# polarization_switch_mid.net
KiCad netlist of a schematic drawn in EAGLE
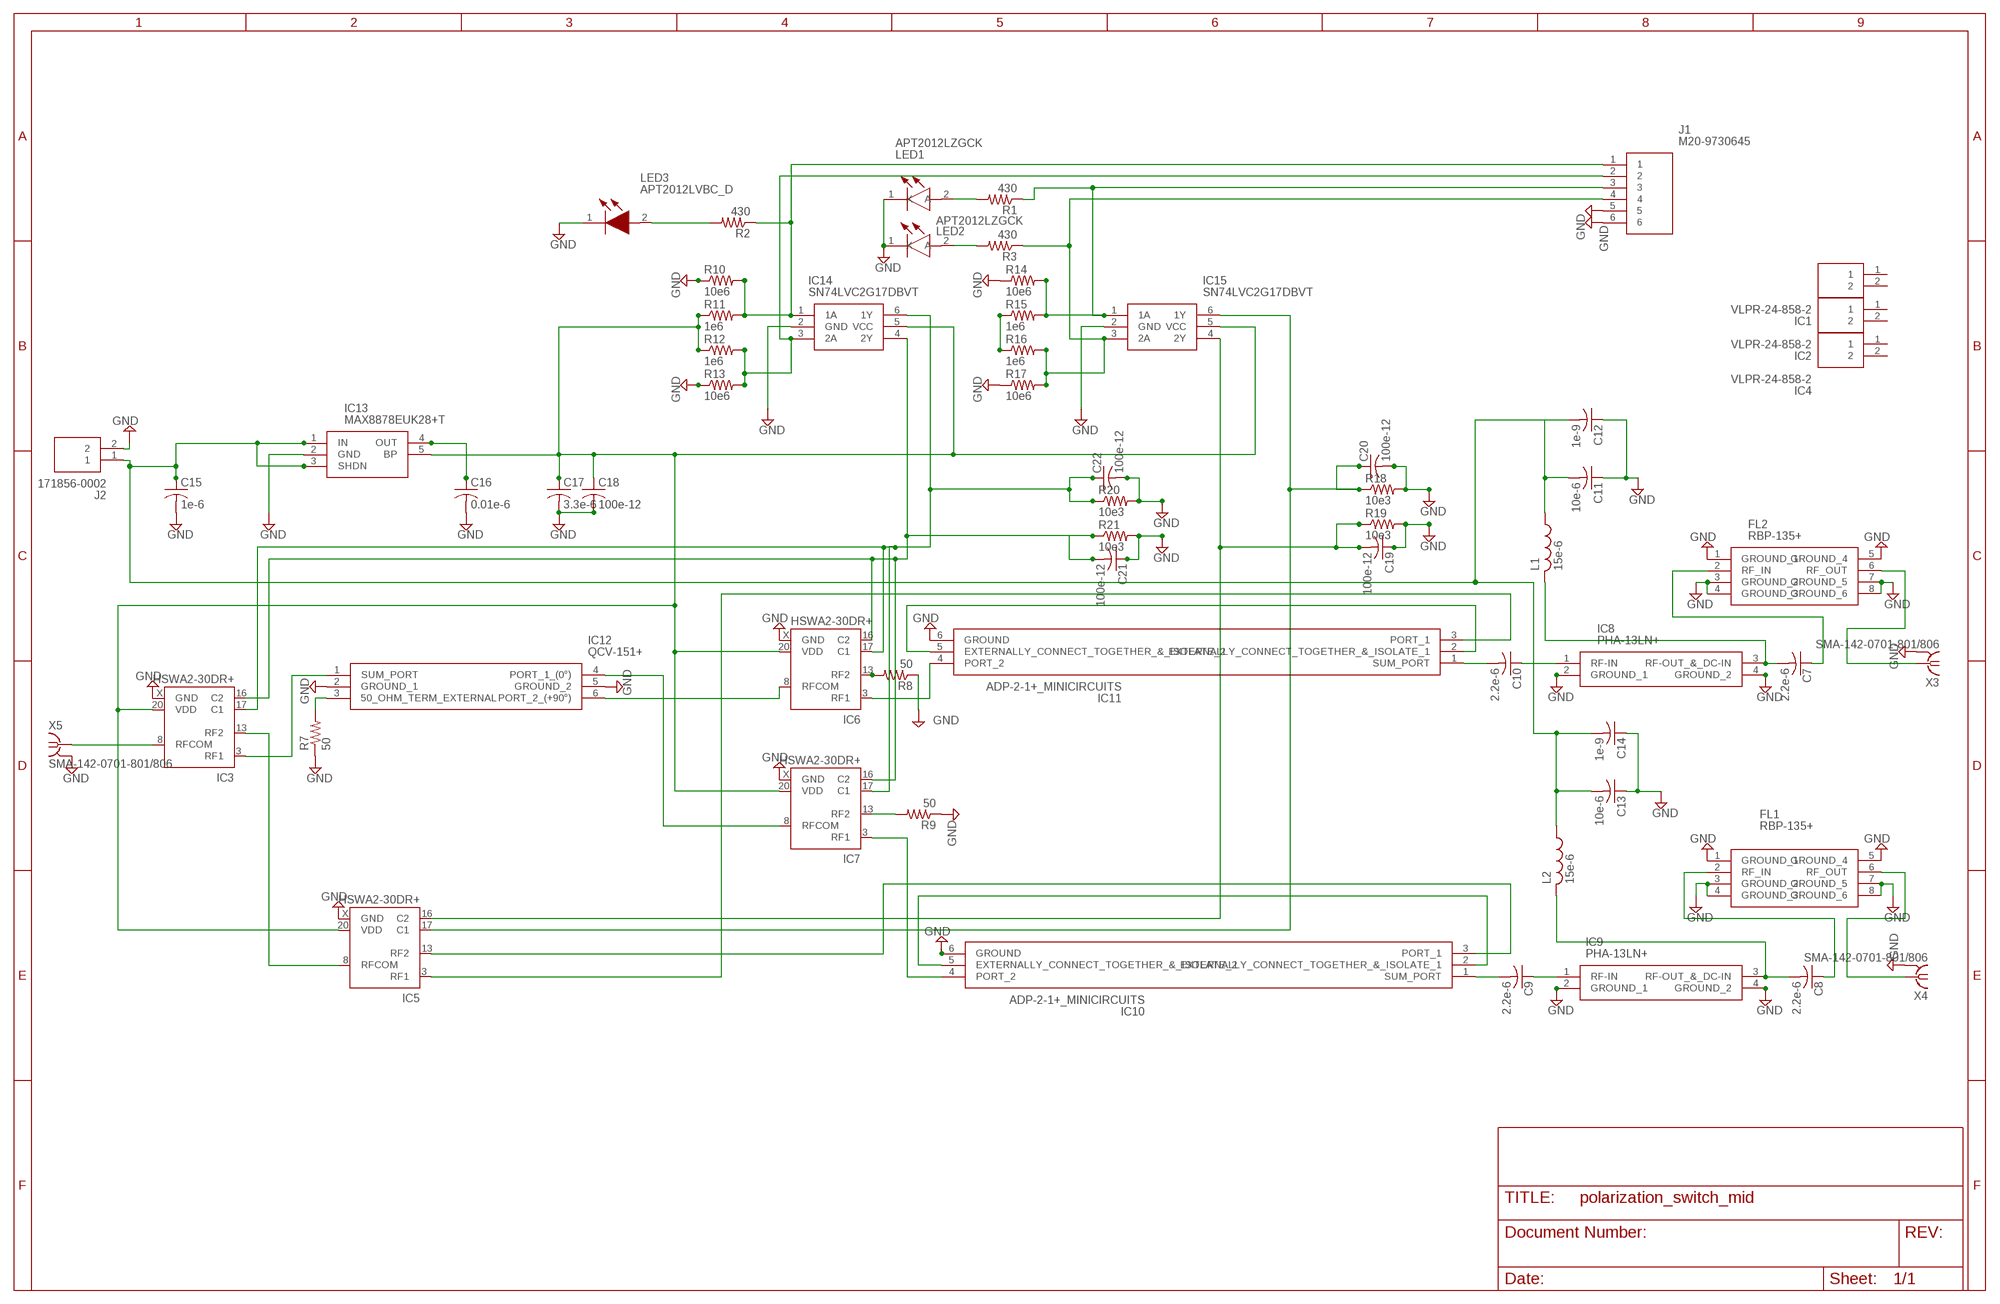
[diagram p0: schematic, sheet 1]

(export (version "E")
  (design (tool "Eeschema 10.0.6"))
  (components
    (comp (ref "C7")
      (value "2.2e-6")
      (footprint "eagle-import:C0603")
      (libsource (lib "eagle-import") (part "C-USC0603"))
    )
    (comp (ref "C8")
      (value "2.2e-6")
      (footprint "eagle-import:C0603")
      (libsource (lib "eagle-import") (part "C-USC0603"))
    )
    (comp (ref "C9")
      (value "2.2e-6")
      (footprint "eagle-import:C0603")
      (libsource (lib "eagle-import") (part "C-USC0603"))
    )
    (comp (ref "C10")
      (value "2.2e-6")
      (footprint "eagle-import:C0603")
      (libsource (lib "eagle-import") (part "C-USC0603"))
    )
    (comp (ref "C11")
      (value "10e-6")
      (footprint "eagle-import:C0603")
      (libsource (lib "eagle-import") (part "C-USC0603"))
    )
    (comp (ref "C12")
      (value "1e-9")
      (footprint "eagle-import:C0603")
      (libsource (lib "eagle-import") (part "C-USC0603"))
    )
    (comp (ref "C13")
      (value "10e-6")
      (footprint "eagle-import:C0603")
      (libsource (lib "eagle-import") (part "C-USC0603"))
    )
    (comp (ref "C14")
      (value "1e-9")
      (footprint "eagle-import:C0603")
      (libsource (lib "eagle-import") (part "C-USC0603"))
    )
    (comp (ref "C15")
      (value "1e-6")
      (footprint "eagle-import:C0603")
      (libsource (lib "eagle-import") (part "C-USC0603"))
    )
    (comp (ref "C16")
      (value "0.01e-6")
      (footprint "eagle-import:C0603")
      (libsource (lib "eagle-import") (part "C-USC0603"))
    )
    (comp (ref "C17")
      (value "3.3e-6")
      (footprint "eagle-import:C0603")
      (libsource (lib "eagle-import") (part "C-USC0603"))
    )
    (comp (ref "C18")
      (value "100e-12")
      (footprint "eagle-import:C0603")
      (libsource (lib "eagle-import") (part "C-USC0603"))
    )
    (comp (ref "C19")
      (value "100e-12")
      (footprint "eagle-import:C0603")
      (libsource (lib "eagle-import") (part "C-USC0603"))
    )
    (comp (ref "C20")
      (value "100e-12")
      (footprint "eagle-import:C0603")
      (libsource (lib "eagle-import") (part "C-USC0603"))
    )
    (comp (ref "C21")
      (value "100e-12")
      (footprint "eagle-import:C0603")
      (libsource (lib "eagle-import") (part "C-USC0603"))
    )
    (comp (ref "C22")
      (value "100e-12")
      (footprint "eagle-import:C0603")
      (libsource (lib "eagle-import") (part "C-USC0603"))
    )
    (comp (ref "FL1")
      (value "RBP-135+")
      (footprint "eagle-import:RBP135")
      (libsource (lib "eagle-import") (part "RBP-135+"))
    )
    (comp (ref "FL2")
      (value "RBP-135+")
      (footprint "eagle-import:RBP135")
      (libsource (lib "eagle-import") (part "RBP-135+"))
    )
    (comp (ref "IC1")
      (value "VLPR-24-858-2")
      (footprint "eagle-import:VLPR248582")
      (fields (field (name "RS_PART_NUMBER") "9063748"))
      (libsource (lib "eagle-import") (part "VLPR-24-858-2"))
    )
    (comp (ref "IC2")
      (value "VLPR-24-858-2")
      (footprint "eagle-import:VLPR248582")
      (fields (field (name "RS_PART_NUMBER") "9063748"))
      (libsource (lib "eagle-import") (part "VLPR-24-858-2"))
    )
    (comp (ref "IC3")
      (value "HSWA2-30DR+")
      (footprint "eagle-import:DG983-1")
      (libsource (lib "eagle-import") (part "HSWA2-30DR+"))
    )
    (comp (ref "IC4")
      (value "VLPR-24-858-2")
      (footprint "eagle-import:VLPR248582")
      (fields (field (name "RS_PART_NUMBER") "9063748"))
      (libsource (lib "eagle-import") (part "VLPR-24-858-2"))
    )
    (comp (ref "IC5")
      (value "HSWA2-30DR+")
      (footprint "eagle-import:DG983-1")
      (libsource (lib "eagle-import") (part "HSWA2-30DR+"))
    )
    (comp (ref "IC6")
      (value "HSWA2-30DR+")
      (footprint "eagle-import:DG983-1")
      (libsource (lib "eagle-import") (part "HSWA2-30DR+"))
    )
    (comp (ref "IC7")
      (value "HSWA2-30DR+")
      (footprint "eagle-import:DG983-1")
      (libsource (lib "eagle-import") (part "HSWA2-30DR+"))
    )
    (comp (ref "IC8")
      (value "PHA-13LN+")
      (footprint "eagle-import:PHA13LN")
      (libsource (lib "eagle-import") (part "PHA-13LN+"))
    )
    (comp (ref "IC9")
      (value "PHA-13LN+")
      (footprint "eagle-import:PHA13LN")
      (libsource (lib "eagle-import") (part "PHA-13LN+"))
    )
    (comp (ref "IC10")
      (value "ADP-2-1+_MINICIRCUITS")
      (footprint "eagle-import:SOTFL254P691X411-6N")
      (fields (field (name "MANUFACTURER_PART_NUMBER") "ADP-2-1+ MINICIRCUITS"))
      (libsource (lib "eagle-import") (part "ADP-2-1+_MINICIRCUITS"))
    )
    (comp (ref "IC11")
      (value "ADP-2-1+_MINICIRCUITS")
      (footprint "eagle-import:SOTFL254P691X411-6N")
      (fields (field (name "MANUFACTURER_PART_NUMBER") "ADP-2-1+ MINICIRCUITS"))
      (libsource (lib "eagle-import") (part "ADP-2-1+_MINICIRCUITS"))
    )
    (comp (ref "IC12")
      (value "QCV-151+")
      (footprint "eagle-import:QCV151")
      (libsource (lib "eagle-import") (part "QCV-151+"))
    )
    (comp (ref "IC13")
      (value "MAX8878EUK28+T")
      (footprint "eagle-import:SOT95P280X145-5N")
      (libsource (lib "eagle-import") (part "MAX8878EUK28+T"))
    )
    (comp (ref "IC14")
      (value "SN74LVC2G17DBVT")
      (footprint "eagle-import:SOT95P280X145-6N")
      (fields
        (field (name "MOUSER_PART_NUMBER") "595-SN74LVC2G17DBVT")
        (field (name "RS_PART_NUMBER") "6628944P")
      )
      (libsource (lib "eagle-import") (part "SN74LVC2G17DBVT"))
    )
    (comp (ref "IC15")
      (value "SN74LVC2G17DBVT")
      (footprint "eagle-import:SOT95P280X145-6N")
      (fields
        (field (name "MOUSER_PART_NUMBER") "595-SN74LVC2G17DBVT")
        (field (name "RS_PART_NUMBER") "6628944P")
      )
      (libsource (lib "eagle-import") (part "SN74LVC2G17DBVT"))
    )
    (comp (ref "J1")
      (value "M20-9730645")
      (footprint "eagle-import:HDRV6W66P0X254_1X6_1524X254X96")
      (fields (field (name "MOUSER_PART_NUMBER") "855-M20-9730645"))
      (libsource (lib "eagle-import") (part "M20-9730645"))
    )
    (comp (ref "J2")
      (value "171856-0002")
      (footprint "eagle-import:SHDR2W90P0X254_1X2_493X635X106")
      (fields
        (field (name "MOUSER_PART_NUMBER") "538-171856-0002")
        (field (name "RS_PART_NUMBER") "7922884P")
      )
      (libsource (lib "eagle-import") (part "171856-0002"))
    )
    (comp (ref "L1")
      (value "15e-6")
      (footprint "eagle-import:L3225M")
      (libsource (lib "eagle-import") (part "L-USL3225M"))
    )
    (comp (ref "L2")
      (value "15e-6")
      (footprint "eagle-import:L3225M")
      (libsource (lib "eagle-import") (part "L-USL3225M"))
    )
    (comp (ref "LED1")
      (value "APT2012LZGCK")
      (footprint "eagle-import:LEDC2012X85N")
      (fields (field (name "MOUSER_PART_NUMBER") "604-APT2012LZGCK"))
      (libsource (lib "eagle-import") (part "APT2012LZGCK"))
    )
    (comp (ref "LED2")
      (value "APT2012LZGCK")
      (footprint "eagle-import:LEDC2012X85N")
      (fields (field (name "MOUSER_PART_NUMBER") "604-APT2012LZGCK"))
      (libsource (lib "eagle-import") (part "APT2012LZGCK"))
    )
    (comp (ref "LED3")
      (value "APT2012LVBC_D")
      (footprint "eagle-import:LEDC2012X85N")
      (fields
        (field (name "ARROW_PART_NUMBER") "APT2012LVBC/D")
        (field (name "MOUSER_PART_NUMBER") "604-APT2012LVBCD")
      )
      (libsource (lib "eagle-import") (part "APT2012LVBC_D"))
    )
    (comp (ref "R1")
      (value "430")
      (footprint "eagle-import:R0603")
      (libsource (lib "eagle-import") (part "R-US_R0603"))
    )
    (comp (ref "R2")
      (value "430")
      (footprint "eagle-import:R0603")
      (libsource (lib "eagle-import") (part "R-US_R0603"))
    )
    (comp (ref "R3")
      (value "430")
      (footprint "eagle-import:R0603")
      (libsource (lib "eagle-import") (part "R-US_R0603"))
    )
    (comp (ref "R7")
      (value "50")
      (footprint "eagle-import:R0603")
      (libsource (lib "eagle-import") (part "R-US_R0603"))
    )
    (comp (ref "R8")
      (value "50")
      (footprint "eagle-import:R0603")
      (libsource (lib "eagle-import") (part "R-US_R0603"))
    )
    (comp (ref "R9")
      (value "50")
      (footprint "eagle-import:R0603")
      (libsource (lib "eagle-import") (part "R-US_R0603"))
    )
    (comp (ref "R10")
      (value "10e6")
      (footprint "eagle-import:R0603")
      (libsource (lib "eagle-import") (part "R-US_R0603"))
    )
    (comp (ref "R11")
      (value "1e6")
      (footprint "eagle-import:R0603")
      (libsource (lib "eagle-import") (part "R-US_R0603"))
    )
    (comp (ref "R12")
      (value "1e6")
      (footprint "eagle-import:R0603")
      (libsource (lib "eagle-import") (part "R-US_R0603"))
    )
    (comp (ref "R13")
      (value "10e6")
      (footprint "eagle-import:R0603")
      (libsource (lib "eagle-import") (part "R-US_R0603"))
    )
    (comp (ref "R14")
      (value "10e6")
      (footprint "eagle-import:R0603")
      (libsource (lib "eagle-import") (part "R-US_R0603"))
    )
    (comp (ref "R15")
      (value "1e6")
      (footprint "eagle-import:R0603")
      (libsource (lib "eagle-import") (part "R-US_R0603"))
    )
    (comp (ref "R16")
      (value "1e6")
      (footprint "eagle-import:R0603")
      (libsource (lib "eagle-import") (part "R-US_R0603"))
    )
    (comp (ref "R17")
      (value "10e6")
      (footprint "eagle-import:R0603")
      (libsource (lib "eagle-import") (part "R-US_R0603"))
    )
    (comp (ref "R18")
      (value "10e3")
      (footprint "eagle-import:R0603")
      (libsource (lib "eagle-import") (part "R-US_R0603"))
    )
    (comp (ref "R19")
      (value "10e3")
      (footprint "eagle-import:R0603")
      (libsource (lib "eagle-import") (part "R-US_R0603"))
    )
    (comp (ref "R20")
      (value "10e3")
      (footprint "eagle-import:R0603")
      (libsource (lib "eagle-import") (part "R-US_R0603"))
    )
    (comp (ref "R21")
      (value "10e3")
      (footprint "eagle-import:R0603")
      (libsource (lib "eagle-import") (part "R-US_R0603"))
    )
    (comp (ref "X3")
      (value "SMA-142-0701-801/806")
      (footprint "eagle-import:J502-ND-142-0701-801_806")
      (fields (field (name "MF") "JOHNSON COMPONENTS") (field (name "MPN") "142-0701-801"))
      (libsource (lib "eagle-import") (part "SMA-142-0701-801/806"))
    )
    (comp (ref "X4")
      (value "SMA-142-0701-801/806")
      (footprint "eagle-import:J502-ND-142-0701-801_806")
      (fields (field (name "MF") "JOHNSON COMPONENTS") (field (name "MPN") "142-0701-801"))
      (libsource (lib "eagle-import") (part "SMA-142-0701-801/806"))
    )
    (comp (ref "X5")
      (value "SMA-142-0701-801/806")
      (footprint "eagle-import:J502-ND-142-0701-801_806")
      (fields (field (name "MF") "JOHNSON COMPONENTS") (field (name "MPN") "142-0701-801"))
      (libsource (lib "eagle-import") (part "SMA-142-0701-801/806"))
    )
  )
  (nets
    (net (code "1") (name "GND") (class "Default")
      (node (ref "C11") (pin "1") (pinfunction "1_1") (pintype "passive"))
      (node (ref "C12") (pin "1") (pinfunction "1_1") (pintype "passive"))
      (node (ref "C13") (pin "1") (pinfunction "1_1") (pintype "passive"))
      (node (ref "C14") (pin "1") (pinfunction "1_1") (pintype "passive"))
      (node (ref "C15") (pin "2") (pinfunction "2_2") (pintype "passive"))
      (node (ref "C16") (pin "2") (pinfunction "2_2") (pintype "passive"))
      (node (ref "C17") (pin "2") (pinfunction "2_2") (pintype "passive"))
      (node (ref "C18") (pin "2") (pinfunction "2_2") (pintype "passive"))
      (node (ref "C19") (pin "1") (pinfunction "1_1") (pintype "passive"))
      (node (ref "C20") (pin "2") (pinfunction "2_2") (pintype "passive"))
      (node (ref "C21") (pin "1") (pinfunction "1_1") (pintype "passive"))
      (node (ref "C22") (pin "2") (pinfunction "2_2") (pintype "passive"))
      (node (ref "FL1") (pin "1") (pinfunction "GROUND_1_1") (pintype "bidirectional"))
      (node (ref "FL1") (pin "3") (pinfunction "GROUND_2_3") (pintype "bidirectional"))
      (node (ref "FL1") (pin "4") (pinfunction "GROUND_3_4") (pintype "bidirectional"))
      (node (ref "FL1") (pin "5") (pinfunction "GROUND_4_5") (pintype "bidirectional"))
      (node (ref "FL1") (pin "7") (pinfunction "GROUND_5_7") (pintype "bidirectional"))
      (node (ref "FL1") (pin "8") (pinfunction "GROUND_6_8") (pintype "bidirectional"))
      (node (ref "FL2") (pin "1") (pinfunction "GROUND_1_1") (pintype "bidirectional"))
      (node (ref "FL2") (pin "3") (pinfunction "GROUND_2_3") (pintype "bidirectional"))
      (node (ref "FL2") (pin "4") (pinfunction "GROUND_3_4") (pintype "bidirectional"))
      (node (ref "FL2") (pin "5") (pinfunction "GROUND_4_5") (pintype "bidirectional"))
      (node (ref "FL2") (pin "7") (pinfunction "GROUND_5_7") (pintype "bidirectional"))
      (node (ref "FL2") (pin "8") (pinfunction "GROUND_6_8") (pintype "bidirectional"))
      (node (ref "IC10") (pin "6") (pinfunction "GROUND_6") (pintype "bidirectional"))
      (node (ref "IC11") (pin "6") (pinfunction "GROUND_6") (pintype "bidirectional"))
      (node (ref "IC12") (pin "2") (pinfunction "GROUND_1_2") (pintype "bidirectional"))
      (node (ref "IC12") (pin "5") (pinfunction "GROUND_2_5") (pintype "bidirectional"))
      (node (ref "IC13") (pin "2") (pinfunction "GND_2") (pintype "power_in"))
      (node (ref "IC14") (pin "2") (pinfunction "GND_2") (pintype "bidirectional"))
      (node (ref "IC15") (pin "2") (pinfunction "GND_2") (pintype "bidirectional"))
      (node (ref "IC3") (pin "X") (pinfunction "GND_X") (pintype "power_in"))
      (node (ref "IC5") (pin "X") (pinfunction "GND_X") (pintype "power_in"))
      (node (ref "IC6") (pin "X") (pinfunction "GND_X") (pintype "power_in"))
      (node (ref "IC7") (pin "X") (pinfunction "GND_X") (pintype "power_in"))
      (node (ref "IC8") (pin "2") (pinfunction "GROUND_1_2") (pintype "bidirectional"))
      (node (ref "IC8") (pin "4") (pinfunction "GROUND_2_4") (pintype "bidirectional"))
      (node (ref "IC9") (pin "2") (pinfunction "GROUND_1_2") (pintype "bidirectional"))
      (node (ref "IC9") (pin "4") (pinfunction "GROUND_2_4") (pintype "bidirectional"))
      (node (ref "J1") (pin "5") (pinfunction "5_5") (pintype "bidirectional"))
      (node (ref "J1") (pin "6") (pinfunction "6_6") (pintype "bidirectional"))
      (node (ref "J2") (pin "2") (pinfunction "2_2") (pintype "bidirectional"))
      (node (ref "LED1") (pin "1") (pinfunction "K_1") (pintype "bidirectional"))
      (node (ref "LED2") (pin "1") (pinfunction "K_1") (pintype "bidirectional"))
      (node (ref "LED3") (pin "1") (pinfunction "K_1") (pintype "bidirectional"))
      (node (ref "R10") (pin "1") (pinfunction "1_1") (pintype "passive"))
      (node (ref "R13") (pin "1") (pinfunction "1_1") (pintype "passive"))
      (node (ref "R14") (pin "1") (pinfunction "1_1") (pintype "passive"))
      (node (ref "R17") (pin "1") (pinfunction "1_1") (pintype "passive"))
      (node (ref "R18") (pin "2") (pinfunction "2_2") (pintype "passive"))
      (node (ref "R19") (pin "2") (pinfunction "2_2") (pintype "passive"))
      (node (ref "R20") (pin "2") (pinfunction "2_2") (pintype "passive"))
      (node (ref "R21") (pin "2") (pinfunction "2_2") (pintype "passive"))
      (node (ref "R7") (pin "1") (pinfunction "1_1") (pintype "passive"))
      (node (ref "R8") (pin "1") (pinfunction "1_1") (pintype "passive"))
      (node (ref "R9") (pin "1") (pinfunction "1_1") (pintype "passive"))
      (node (ref "X3") (pin "G@1") (pinfunction "2_G@1") (pintype "passive"))
      (node (ref "X3") (pin "G@2") (pinfunction "2_G@2") (pintype "passive"))
      (node (ref "X3") (pin "G@3") (pinfunction "2_G@3") (pintype "passive"))
      (node (ref "X3") (pin "G@4") (pinfunction "2_G@4") (pintype "passive"))
      (node (ref "X4") (pin "G@1") (pinfunction "2_G@1") (pintype "passive"))
      (node (ref "X4") (pin "G@2") (pinfunction "2_G@2") (pintype "passive"))
      (node (ref "X4") (pin "G@3") (pinfunction "2_G@3") (pintype "passive"))
      (node (ref "X4") (pin "G@4") (pinfunction "2_G@4") (pintype "passive"))
      (node (ref "X5") (pin "G@1") (pinfunction "2_G@1") (pintype "passive"))
      (node (ref "X5") (pin "G@2") (pinfunction "2_G@2") (pintype "passive"))
      (node (ref "X5") (pin "G@3") (pinfunction "2_G@3") (pintype "passive"))
      (node (ref "X5") (pin "G@4") (pinfunction "2_G@4") (pintype "passive"))
    )
    (net (code "2") (name "Net-(FL1-RF_IN)") (class "Default")
      (node (ref "C8") (pin "1") (pinfunction "1_1") (pintype "passive"))
      (node (ref "FL1") (pin "2") (pinfunction "RF_IN_2") (pintype "bidirectional"))
    )
    (net (code "3") (name "Net-(FL1-RF_OUT)") (class "Default")
      (node (ref "FL1") (pin "6") (pinfunction "RF_OUT_6") (pintype "bidirectional"))
      (node (ref "X4") (pin "1") (pinfunction "1_1") (pintype "passive"))
    )
    (net (code "4") (name "Net-(FL2-RF_IN)") (class "Default")
      (node (ref "C7") (pin "1") (pinfunction "1_1") (pintype "passive"))
      (node (ref "FL2") (pin "2") (pinfunction "RF_IN_2") (pintype "bidirectional"))
    )
    (net (code "5") (name "Net-(FL2-RF_OUT)") (class "Default")
      (node (ref "FL2") (pin "6") (pinfunction "RF_OUT_6") (pintype "bidirectional"))
      (node (ref "X3") (pin "1") (pinfunction "1_1") (pintype "passive"))
    )
    (net (code "6") (name "Net-(IC3A-RF2)") (class "Default")
      (node (ref "IC3") (pin "13") (pinfunction "RF2_13") (pintype "passive"))
      (node (ref "IC5") (pin "8") (pinfunction "RFCOM_8") (pintype "passive"))
    )
    (net (code "7") (name "Net-(IC3A-RFCOM)") (class "Default")
      (node (ref "IC3") (pin "8") (pinfunction "RFCOM_8") (pintype "passive"))
      (node (ref "X5") (pin "1") (pinfunction "1_1") (pintype "passive"))
    )
    (net (code "8") (name "Net-(IC6A-RF2)") (class "Default")
      (node (ref "IC6") (pin "13") (pinfunction "RF2_13") (pintype "passive"))
      (node (ref "R8") (pin "2") (pinfunction "2_2") (pintype "passive"))
    )
    (net (code "9") (name "Net-(IC7A-RF2)") (class "Default")
      (node (ref "IC7") (pin "13") (pinfunction "RF2_13") (pintype "passive"))
      (node (ref "R9") (pin "2") (pinfunction "2_2") (pintype "passive"))
    )
    (net (code "10") (name "Net-(IC8-RF-IN)") (class "Default")
      (node (ref "C10") (pin "1") (pinfunction "1_1") (pintype "passive"))
      (node (ref "IC8") (pin "1") (pinfunction "RF-IN_1") (pintype "bidirectional"))
    )
    (net (code "11") (name "Net-(IC8-RF-OUT_&_DC-IN)") (class "Default")
      (node (ref "C7") (pin "2") (pinfunction "2_2") (pintype "passive"))
      (node (ref "IC8") (pin "3") (pinfunction "RF-OUT_&_DC-IN_3") (pintype "bidirectional"))
      (node (ref "L1") (pin "2") (pinfunction "2_2") (pintype "passive"))
    )
    (net (code "12") (name "Net-(IC9-RF-IN)") (class "Default")
      (node (ref "C9") (pin "1") (pinfunction "1_1") (pintype "passive"))
      (node (ref "IC9") (pin "1") (pinfunction "RF-IN_1") (pintype "bidirectional"))
    )
    (net (code "13") (name "Net-(IC9-RF-OUT_&_DC-IN)") (class "Default")
      (node (ref "C8") (pin "2") (pinfunction "2_2") (pintype "passive"))
      (node (ref "IC9") (pin "3") (pinfunction "RF-OUT_&_DC-IN_3") (pintype "bidirectional"))
      (node (ref "L2") (pin "2") (pinfunction "2_2") (pintype "passive"))
    )
    (net (code "14") (name "Net-(IC10-EXTERNALLY_CONNECT_TOGETHER_&_ISOLATE_1)") (class "Default")
      (node (ref "IC10") (pin "2") (pinfunction "EXTERNALLY_CONNECT_TOGETHER_&_ISOLATE_1_2") (pintype "bidirectional"))
      (node (ref "IC10") (pin "5") (pinfunction "EXTERNALLY_CONNECT_TOGETHER_&_ISOLATE_2_5") (pintype "bidirectional"))
    )
    (net (code "15") (name "Net-(IC10-PORT_1)") (class "Default")
      (node (ref "IC10") (pin "3") (pinfunction "PORT_1_3") (pintype "bidirectional"))
      (node (ref "IC5") (pin "13") (pinfunction "RF2_13") (pintype "passive"))
    )
    (net (code "16") (name "Net-(IC10-PORT_2)") (class "Default")
      (node (ref "IC10") (pin "4") (pinfunction "PORT_2_4") (pintype "bidirectional"))
      (node (ref "IC7") (pin "3") (pinfunction "RF1_3") (pintype "passive"))
    )
    (net (code "17") (name "Net-(IC10-SUM_PORT)") (class "Default")
      (node (ref "C9") (pin "2") (pinfunction "2_2") (pintype "passive"))
      (node (ref "IC10") (pin "1") (pinfunction "SUM_PORT_1") (pintype "bidirectional"))
    )
    (net (code "18") (name "Net-(IC11-EXTERNALLY_CONNECT_TOGETHER_&_ISOLATE_1)") (class "Default")
      (node (ref "IC11") (pin "2") (pinfunction "EXTERNALLY_CONNECT_TOGETHER_&_ISOLATE_1_2") (pintype "bidirectional"))
      (node (ref "IC11") (pin "5") (pinfunction "EXTERNALLY_CONNECT_TOGETHER_&_ISOLATE_2_5") (pintype "bidirectional"))
    )
    (net (code "19") (name "Net-(IC11-PORT_1)") (class "Default")
      (node (ref "IC11") (pin "3") (pinfunction "PORT_1_3") (pintype "bidirectional"))
      (node (ref "IC5") (pin "3") (pinfunction "RF1_3") (pintype "passive"))
    )
    (net (code "20") (name "Net-(IC11-PORT_2)") (class "Default")
      (node (ref "IC11") (pin "4") (pinfunction "PORT_2_4") (pintype "bidirectional"))
      (node (ref "IC6") (pin "3") (pinfunction "RF1_3") (pintype "passive"))
    )
    (net (code "21") (name "Net-(IC11-SUM_PORT)") (class "Default")
      (node (ref "C10") (pin "2") (pinfunction "2_2") (pintype "passive"))
      (node (ref "IC11") (pin "1") (pinfunction "SUM_PORT_1") (pintype "bidirectional"))
    )
    (net (code "22") (name "Net-(IC12-50_OHM_TERM_EXTERNAL)") (class "Default")
      (node (ref "IC12") (pin "3") (pinfunction "50_OHM_TERM_EXTERNAL_3") (pintype "bidirectional"))
      (node (ref "R7") (pin "2") (pinfunction "2_2") (pintype "passive"))
    )
    (net (code "23") (name "Net-(IC12-PORT_1_(0°))") (class "Default")
      (node (ref "IC12") (pin "4") (pinfunction "PORT_1_(0°)_4") (pintype "bidirectional"))
      (node (ref "IC7") (pin "8") (pinfunction "RFCOM_8") (pintype "passive"))
    )
    (net (code "24") (name "Net-(IC12-PORT_2_(+90°))") (class "Default")
      (node (ref "IC12") (pin "6") (pinfunction "PORT_2_(+90°)_6") (pintype "bidirectional"))
      (node (ref "IC6") (pin "8") (pinfunction "RFCOM_8") (pintype "passive"))
    )
    (net (code "25") (name "Net-(IC12-SUM_PORT)") (class "Default")
      (node (ref "IC12") (pin "1") (pinfunction "SUM_PORT_1") (pintype "bidirectional"))
      (node (ref "IC3") (pin "3") (pinfunction "RF1_3") (pintype "passive"))
    )
    (net (code "26") (name "Net-(IC13-BP)") (class "Default")
      (node (ref "C17") (pin "1") (pinfunction "1_1") (pintype "passive"))
      (node (ref "C18") (pin "1") (pinfunction "1_1") (pintype "passive"))
      (node (ref "IC13") (pin "5") (pinfunction "BP_5") (pintype "bidirectional"))
      (node (ref "IC14") (pin "5") (pinfunction "VCC_5") (pintype "bidirectional"))
      (node (ref "IC15") (pin "5") (pinfunction "VCC_5") (pintype "bidirectional"))
      (node (ref "IC3") (pin "20") (pinfunction "VDD_20") (pintype "input"))
      (node (ref "IC5") (pin "20") (pinfunction "VDD_20") (pintype "input"))
      (node (ref "IC6") (pin "20") (pinfunction "VDD_20") (pintype "input"))
      (node (ref "IC7") (pin "20") (pinfunction "VDD_20") (pintype "input"))
      (node (ref "R11") (pin "1") (pinfunction "1_1") (pintype "passive"))
      (node (ref "R12") (pin "1") (pinfunction "1_1") (pintype "passive"))
    )
    (net (code "27") (name "Net-(IC13-IN)") (class "Default")
      (node (ref "C11") (pin "2") (pinfunction "2_2") (pintype "passive"))
      (node (ref "C12") (pin "2") (pinfunction "2_2") (pintype "passive"))
      (node (ref "C13") (pin "2") (pinfunction "2_2") (pintype "passive"))
      (node (ref "C14") (pin "2") (pinfunction "2_2") (pintype "passive"))
      (node (ref "C15") (pin "1") (pinfunction "1_1") (pintype "passive"))
      (node (ref "IC13") (pin "1") (pinfunction "IN_1") (pintype "input"))
      (node (ref "IC13") (pin "3") (pinfunction "SHDN_3") (pintype "bidirectional"))
      (node (ref "J2") (pin "1") (pinfunction "1_1") (pintype "bidirectional"))
      (node (ref "L1") (pin "1") (pinfunction "1_1") (pintype "passive"))
      (node (ref "L2") (pin "1") (pinfunction "1_1") (pintype "passive"))
    )
    (net (code "28") (name "Net-(IC13-OUT)") (class "Default")
      (node (ref "C16") (pin "1") (pinfunction "1_1") (pintype "passive"))
      (node (ref "IC13") (pin "4") (pinfunction "OUT_4") (pintype "output"))
    )
    (net (code "29") (name "Net-(IC14-1A)") (class "Default")
      (node (ref "IC14") (pin "1") (pinfunction "1A_1") (pintype "bidirectional"))
      (node (ref "J1") (pin "1") (pinfunction "1_1") (pintype "bidirectional"))
      (node (ref "R10") (pin "2") (pinfunction "2_2") (pintype "passive"))
      (node (ref "R11") (pin "2") (pinfunction "2_2") (pintype "passive"))
      (node (ref "R2") (pin "1") (pinfunction "1_1") (pintype "passive"))
    )
    (net (code "30") (name "Net-(IC14-1Y)") (class "Default")
      (node (ref "C22") (pin "1") (pinfunction "1_1") (pintype "passive"))
      (node (ref "IC14") (pin "6") (pinfunction "1Y_6") (pintype "bidirectional"))
      (node (ref "IC3") (pin "17") (pinfunction "C1_17") (pintype "passive"))
      (node (ref "IC6") (pin "17") (pinfunction "C1_17") (pintype "passive"))
      (node (ref "IC7") (pin "17") (pinfunction "C1_17") (pintype "passive"))
      (node (ref "R20") (pin "1") (pinfunction "1_1") (pintype "passive"))
    )
    (net (code "31") (name "Net-(IC14-2A)") (class "Default")
      (node (ref "IC14") (pin "3") (pinfunction "2A_3") (pintype "bidirectional"))
      (node (ref "J1") (pin "2") (pinfunction "2_2") (pintype "bidirectional"))
      (node (ref "R12") (pin "2") (pinfunction "2_2") (pintype "passive"))
      (node (ref "R13") (pin "2") (pinfunction "2_2") (pintype "passive"))
    )
    (net (code "32") (name "Net-(IC14-2Y)") (class "Default")
      (node (ref "C21") (pin "2") (pinfunction "2_2") (pintype "passive"))
      (node (ref "IC14") (pin "4") (pinfunction "2Y_4") (pintype "bidirectional"))
      (node (ref "IC3") (pin "16") (pinfunction "C2_16") (pintype "passive"))
      (node (ref "IC6") (pin "16") (pinfunction "C2_16") (pintype "passive"))
      (node (ref "IC7") (pin "16") (pinfunction "C2_16") (pintype "passive"))
      (node (ref "R21") (pin "1") (pinfunction "1_1") (pintype "passive"))
    )
    (net (code "33") (name "Net-(IC15-1A)") (class "Default")
      (node (ref "IC15") (pin "1") (pinfunction "1A_1") (pintype "bidirectional"))
      (node (ref "J1") (pin "3") (pinfunction "3_3") (pintype "bidirectional"))
      (node (ref "R1") (pin "1") (pinfunction "1_1") (pintype "passive"))
      (node (ref "R14") (pin "2") (pinfunction "2_2") (pintype "passive"))
      (node (ref "R15") (pin "2") (pinfunction "2_2") (pintype "passive"))
    )
    (net (code "34") (name "Net-(IC15-1Y)") (class "Default")
      (node (ref "C20") (pin "1") (pinfunction "1_1") (pintype "passive"))
      (node (ref "IC15") (pin "6") (pinfunction "1Y_6") (pintype "bidirectional"))
      (node (ref "IC5") (pin "17") (pinfunction "C1_17") (pintype "passive"))
      (node (ref "R18") (pin "1") (pinfunction "1_1") (pintype "passive"))
    )
    (net (code "35") (name "Net-(IC15-2A)") (class "Default")
      (node (ref "IC15") (pin "3") (pinfunction "2A_3") (pintype "bidirectional"))
      (node (ref "J1") (pin "4") (pinfunction "4_4") (pintype "bidirectional"))
      (node (ref "R16") (pin "2") (pinfunction "2_2") (pintype "passive"))
      (node (ref "R17") (pin "2") (pinfunction "2_2") (pintype "passive"))
      (node (ref "R3") (pin "1") (pinfunction "1_1") (pintype "passive"))
    )
    (net (code "36") (name "Net-(IC15-2Y)") (class "Default")
      (node (ref "C19") (pin "2") (pinfunction "2_2") (pintype "passive"))
      (node (ref "IC15") (pin "4") (pinfunction "2Y_4") (pintype "bidirectional"))
      (node (ref "IC5") (pin "16") (pinfunction "C2_16") (pintype "passive"))
      (node (ref "R19") (pin "1") (pinfunction "1_1") (pintype "passive"))
    )
    (net (code "37") (name "Net-(LED1-A)") (class "Default")
      (node (ref "LED1") (pin "2") (pinfunction "A_2") (pintype "bidirectional"))
      (node (ref "R1") (pin "2") (pinfunction "2_2") (pintype "passive"))
    )
    (net (code "38") (name "Net-(LED2-A)") (class "Default")
      (node (ref "LED2") (pin "2") (pinfunction "A_2") (pintype "bidirectional"))
      (node (ref "R3") (pin "2") (pinfunction "2_2") (pintype "passive"))
    )
    (net (code "39") (name "Net-(LED3-A)") (class "Default")
      (node (ref "LED3") (pin "2") (pinfunction "A_2") (pintype "bidirectional"))
      (node (ref "R2") (pin "2") (pinfunction "2_2") (pintype "passive"))
    )
    (net (code "40") (name "Net-(R15-Pad1)") (class "Default")
      (node (ref "R15") (pin "1") (pinfunction "1_1") (pintype "passive"))
      (node (ref "R16") (pin "1") (pinfunction "1_1") (pintype "passive"))
    )
    (net (code "41") (name "unconnected-(IC1-Pad1)") (class "Default")
      (node (ref "IC1") (pin "1") (pinfunction "1_1") (pintype "bidirectional"))
    )
    (net (code "42") (name "unconnected-(IC1-Pad2)") (class "Default")
      (node (ref "IC1") (pin "2") (pinfunction "2_2") (pintype "bidirectional"))
    )
    (net (code "43") (name "unconnected-(IC2-Pad1)") (class "Default")
      (node (ref "IC2") (pin "1") (pinfunction "1_1") (pintype "bidirectional"))
    )
    (net (code "44") (name "unconnected-(IC2-Pad2)") (class "Default")
      (node (ref "IC2") (pin "2") (pinfunction "2_2") (pintype "bidirectional"))
    )
    (net (code "45") (name "unconnected-(IC4-Pad1)") (class "Default")
      (node (ref "IC4") (pin "1") (pinfunction "1_1") (pintype "bidirectional"))
    )
    (net (code "46") (name "unconnected-(IC4-Pad2)") (class "Default")
      (node (ref "IC4") (pin "2") (pinfunction "2_2") (pintype "bidirectional"))
    )
  )
)
